# upromswr.net
KiCad netlist of a schematic drawn in EAGLE
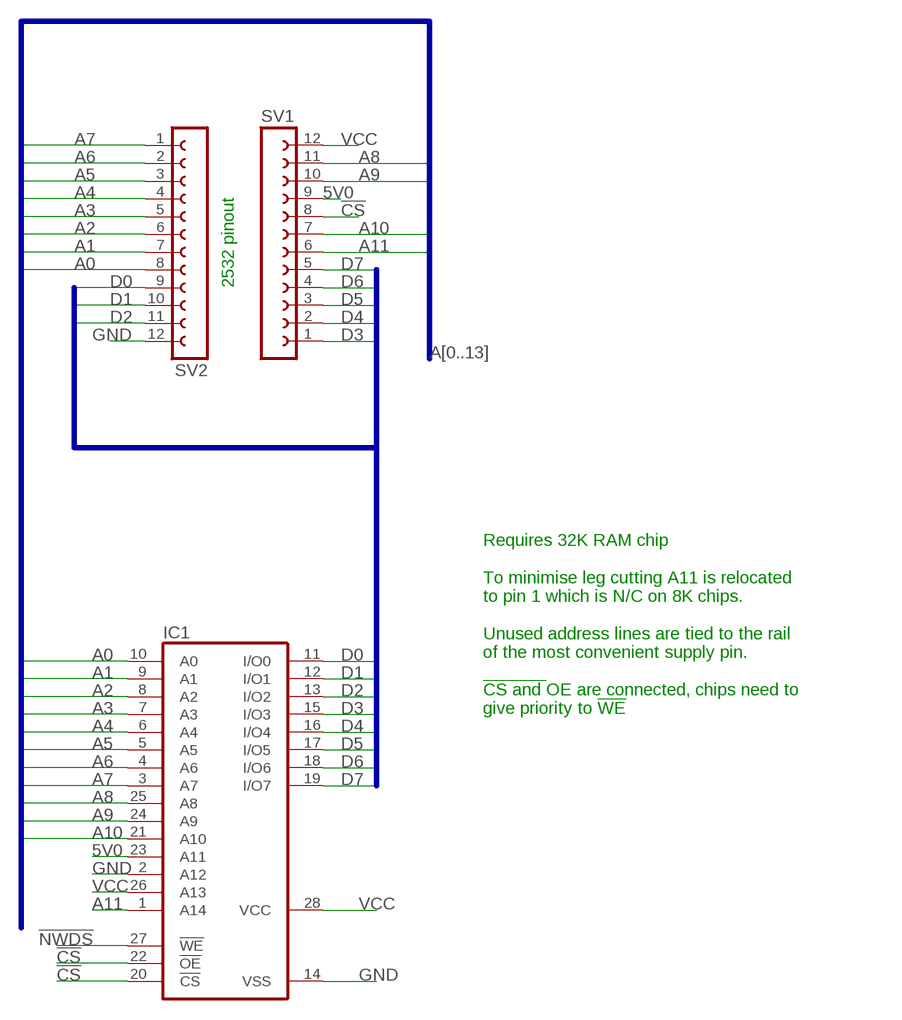
[diagram p0: schematic, sheet 1]

(export (version "E")
  (design (tool "Eeschema 10.0.6"))
  (components
    (comp (ref "IC1")
      (value "62256P")
      (footprint "eagle-import:DIL28-6")
      (libsource (lib "eagle-import") (part "62256P"))
    )
    (comp (ref "SV1")
      (value "FE12-1")
      (footprint "eagle-import:FE12")
      (libsource (lib "eagle-import") (part "FE12-1"))
    )
    (comp (ref "SV2")
      (value "FE12-1")
      (footprint "eagle-import:FE12")
      (libsource (lib "eagle-import") (part "FE12-1"))
    )
  )
  (nets
    (net (code "3") (name "/5V0") (class "Default")
      (node (ref "IC1") (pin "23") (pinfunction "A11_23") (pintype "input"))
      (node (ref "SV1") (pin "9") (pinfunction "9_9") (pintype "passive"))
    )
    (net (code "4") (name "/A0") (class "Default")
      (node (ref "IC1") (pin "10") (pinfunction "A0_10") (pintype "input"))
      (node (ref "SV2") (pin "8") (pinfunction "8_8") (pintype "passive"))
    )
    (net (code "5") (name "/A1") (class "Default")
      (node (ref "IC1") (pin "9") (pinfunction "A1_9") (pintype "input"))
      (node (ref "SV2") (pin "7") (pinfunction "7_7") (pintype "passive"))
    )
    (net (code "6") (name "/A2") (class "Default")
      (node (ref "IC1") (pin "8") (pinfunction "A2_8") (pintype "input"))
      (node (ref "SV2") (pin "6") (pinfunction "6_6") (pintype "passive"))
    )
    (net (code "7") (name "/A3") (class "Default")
      (node (ref "IC1") (pin "7") (pinfunction "A3_7") (pintype "input"))
      (node (ref "SV2") (pin "5") (pinfunction "5_5") (pintype "passive"))
    )
    (net (code "8") (name "/A4") (class "Default")
      (node (ref "IC1") (pin "6") (pinfunction "A4_6") (pintype "input"))
      (node (ref "SV2") (pin "4") (pinfunction "4_4") (pintype "passive"))
    )
    (net (code "9") (name "/A5") (class "Default")
      (node (ref "IC1") (pin "5") (pinfunction "A5_5") (pintype "input"))
      (node (ref "SV2") (pin "3") (pinfunction "3_3") (pintype "passive"))
    )
    (net (code "10") (name "/A6") (class "Default")
      (node (ref "IC1") (pin "4") (pinfunction "A6_4") (pintype "input"))
      (node (ref "SV2") (pin "2") (pinfunction "2_2") (pintype "passive"))
    )
    (net (code "11") (name "/A7") (class "Default")
      (node (ref "IC1") (pin "3") (pinfunction "A7_3") (pintype "input"))
      (node (ref "SV2") (pin "1") (pinfunction "1_1") (pintype "passive"))
    )
    (net (code "12") (name "/A8") (class "Default")
      (node (ref "IC1") (pin "25") (pinfunction "A8_25") (pintype "input"))
      (node (ref "SV1") (pin "11") (pinfunction "11_11") (pintype "passive"))
    )
    (net (code "13") (name "/A9") (class "Default")
      (node (ref "IC1") (pin "24") (pinfunction "A9_24") (pintype "input"))
      (node (ref "SV1") (pin "10") (pinfunction "10_10") (pintype "passive"))
    )
    (net (code "14") (name "/A10") (class "Default")
      (node (ref "IC1") (pin "21") (pinfunction "A10_21") (pintype "input"))
      (node (ref "SV1") (pin "7") (pinfunction "7_7") (pintype "passive"))
    )
    (net (code "15") (name "/A11") (class "Default")
      (node (ref "IC1") (pin "1") (pinfunction "A14_1") (pintype "input"))
      (node (ref "SV1") (pin "6") (pinfunction "6_6") (pintype "passive"))
    )
    (net (code "17") (name "/D0") (class "Default")
      (node (ref "IC1") (pin "11") (pinfunction "I/O0_11") (pintype "bidirectional"))
      (node (ref "SV2") (pin "9") (pinfunction "9_9") (pintype "passive"))
    )
    (net (code "18") (name "/D1") (class "Default")
      (node (ref "IC1") (pin "12") (pinfunction "I/O1_12") (pintype "bidirectional"))
      (node (ref "SV2") (pin "10") (pinfunction "10_10") (pintype "passive"))
    )
    (net (code "19") (name "/D2") (class "Default")
      (node (ref "IC1") (pin "13") (pinfunction "I/O2_13") (pintype "bidirectional"))
      (node (ref "SV2") (pin "11") (pinfunction "11_11") (pintype "passive"))
    )
    (net (code "20") (name "/D3") (class "Default")
      (node (ref "IC1") (pin "15") (pinfunction "I/O3_15") (pintype "bidirectional"))
      (node (ref "SV1") (pin "1") (pinfunction "1_1") (pintype "passive"))
    )
    (net (code "21") (name "/D4") (class "Default")
      (node (ref "IC1") (pin "16") (pinfunction "I/O4_16") (pintype "bidirectional"))
      (node (ref "SV1") (pin "2") (pinfunction "2_2") (pintype "passive"))
    )
    (net (code "22") (name "/D5") (class "Default")
      (node (ref "IC1") (pin "17") (pinfunction "I/O5_17") (pintype "bidirectional"))
      (node (ref "SV1") (pin "3") (pinfunction "3_3") (pintype "passive"))
    )
    (net (code "23") (name "/D6") (class "Default")
      (node (ref "IC1") (pin "18") (pinfunction "I/O6_18") (pintype "bidirectional"))
      (node (ref "SV1") (pin "4") (pinfunction "4_4") (pintype "passive"))
    )
    (net (code "24") (name "/D7") (class "Default")
      (node (ref "IC1") (pin "19") (pinfunction "I/O7_19") (pintype "bidirectional"))
      (node (ref "SV1") (pin "5") (pinfunction "5_5") (pintype "passive"))
    )
    (net (code "25") (name "/GND") (class "Default")
      (node (ref "IC1") (pin "14") (pinfunction "VSS_14") (pintype "power_in"))
      (node (ref "IC1") (pin "2") (pinfunction "A12_2") (pintype "input"))
      (node (ref "SV2") (pin "12") (pinfunction "12_12") (pintype "passive"))
    )
    (net (code "26") (name "/VCC") (class "Default")
      (node (ref "IC1") (pin "26") (pinfunction "A13_26") (pintype "input"))
      (node (ref "IC1") (pin "28") (pinfunction "VCC_28") (pintype "power_in"))
      (node (ref "SV1") (pin "12") (pinfunction "12_12") (pintype "passive"))
    )
    (net (code "27") (name "/~{CS}") (class "Default")
      (node (ref "IC1") (pin "20") (pinfunction "~{CS}_20") (pintype "input"))
      (node (ref "IC1") (pin "22") (pinfunction "~{OE}_22") (pintype "input"))
      (node (ref "SV1") (pin "8") (pinfunction "8_8") (pintype "passive"))
    )
    (net (code "28") (name "/~{NWDS}") (class "Default")
      (node (ref "IC1") (pin "27") (pinfunction "~{WE}_27") (pintype "input"))
    )
  )
)
